# atmega328p_TH.net
KiCad netlist of a schematic drawn in EAGLE
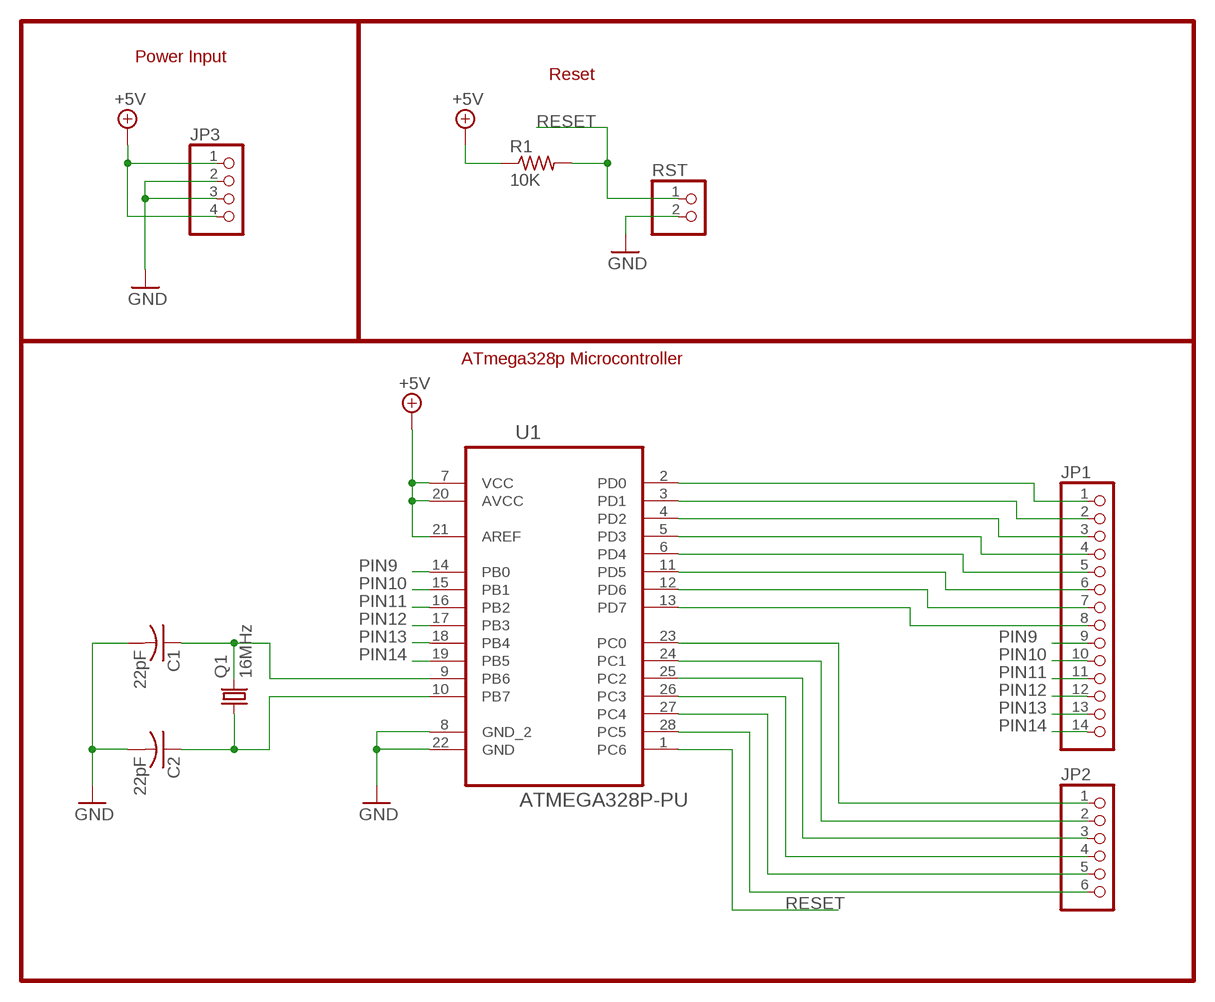
[diagram p0: schematic, sheet 1]

(export (version "E")
  (design (tool "Eeschema 10.0.6"))
  (components
    (comp (ref "C1")
      (value "22pF")
      (footprint "eagle-import:C025-024X044")
      (libsource (lib "eagle-import") (part "C-US025-024X044"))
    )
    (comp (ref "C2")
      (value "22pF")
      (footprint "eagle-import:C025-024X044")
      (libsource (lib "eagle-import") (part "C-US025-024X044"))
    )
    (comp (ref "JP1")
      (value "PINHD-1X14")
      (footprint "eagle-import:1X14")
      (libsource (lib "eagle-import") (part "PINHD-1X14"))
    )
    (comp (ref "JP2")
      (value "PINHD-1X6")
      (footprint "eagle-import:1X06")
      (libsource (lib "eagle-import") (part "PINHD-1X6"))
    )
    (comp (ref "JP3")
      (value "PINHD-1X4")
      (footprint "eagle-import:1X04")
      (libsource (lib "eagle-import") (part "PINHD-1X4"))
    )
    (comp (ref "Q1")
      (value "16MHz")
      (footprint "eagle-import:HC49_S")
      (libsource (lib "eagle-import") (part "CRYSTALHC49S"))
    )
    (comp (ref "R1")
      (value "10K")
      (footprint "eagle-import:0204_7")
      (libsource (lib "eagle-import") (part "R-US_0204/7"))
    )
    (comp (ref "RST")
      (value "PINHD-1X2")
      (footprint "eagle-import:1X02")
      (libsource (lib "eagle-import") (part "PINHD-1X2"))
    )
    (comp (ref "U1")
      (value "ATMEGA328P-PU")
      (footprint "eagle-import:DIP254P762X457-28")
      (libsource (lib "eagle-import") (part "ATMEGA328P-PU"))
    )
  )
  (nets
    (net (code "1") (name "+5V") (class "Default")
      (node (ref "JP3") (pin "1") (pinfunction "1_1") (pintype "passive"))
      (node (ref "JP3") (pin "4") (pinfunction "4_4") (pintype "passive"))
      (node (ref "R1") (pin "1") (pinfunction "1_1") (pintype "passive"))
      (node (ref "U1") (pin "20") (pinfunction "AVCC_20") (pintype "power_in"))
      (node (ref "U1") (pin "21") (pinfunction "AREF_21") (pintype "input"))
      (node (ref "U1") (pin "7") (pinfunction "VCC_7") (pintype "power_in"))
    )
    (net (code "2") (name "/PIN9") (class "Default")
      (node (ref "JP1") (pin "9") (pinfunction "9_9") (pintype "passive"))
      (node (ref "U1") (pin "14") (pinfunction "PB0_14") (pintype "bidirectional"))
    )
    (net (code "3") (name "/PIN10") (class "Default")
      (node (ref "JP1") (pin "10") (pinfunction "10_10") (pintype "passive"))
      (node (ref "U1") (pin "15") (pinfunction "PB1_15") (pintype "bidirectional"))
    )
    (net (code "4") (name "/PIN11") (class "Default")
      (node (ref "JP1") (pin "11") (pinfunction "11_11") (pintype "passive"))
      (node (ref "U1") (pin "16") (pinfunction "PB2_16") (pintype "bidirectional"))
    )
    (net (code "5") (name "/PIN12") (class "Default")
      (node (ref "JP1") (pin "12") (pinfunction "12_12") (pintype "passive"))
      (node (ref "U1") (pin "17") (pinfunction "PB3_17") (pintype "bidirectional"))
    )
    (net (code "6") (name "/PIN13") (class "Default")
      (node (ref "JP1") (pin "13") (pinfunction "13_13") (pintype "passive"))
      (node (ref "U1") (pin "18") (pinfunction "PB4_18") (pintype "bidirectional"))
    )
    (net (code "7") (name "/PIN14") (class "Default")
      (node (ref "JP1") (pin "14") (pinfunction "14_14") (pintype "passive"))
      (node (ref "U1") (pin "19") (pinfunction "PB5_19") (pintype "bidirectional"))
    )
    (net (code "8") (name "/RESET") (class "Default")
      (node (ref "R1") (pin "2") (pinfunction "2_2") (pintype "passive"))
      (node (ref "RST") (pin "1") (pinfunction "1_1") (pintype "passive"))
      (node (ref "U1") (pin "1") (pinfunction "PC6_1") (pintype "bidirectional"))
    )
    (net (code "9") (name "GND") (class "Default")
      (node (ref "C1") (pin "2") (pinfunction "2_2") (pintype "passive"))
      (node (ref "C2") (pin "2") (pinfunction "2_2") (pintype "passive"))
      (node (ref "JP3") (pin "2") (pinfunction "2_2") (pintype "passive"))
      (node (ref "JP3") (pin "3") (pinfunction "3_3") (pintype "passive"))
      (node (ref "RST") (pin "2") (pinfunction "2_2") (pintype "passive"))
      (node (ref "U1") (pin "22") (pinfunction "GND_22") (pintype "passive"))
      (node (ref "U1") (pin "8") (pinfunction "GND_2_8") (pintype "passive"))
    )
    (net (code "10") (name "Net-(U1-PB6)") (class "Default")
      (node (ref "C1") (pin "1") (pinfunction "1_1") (pintype "passive"))
      (node (ref "Q1") (pin "2") (pinfunction "2_2") (pintype "passive"))
      (node (ref "U1") (pin "9") (pinfunction "PB6_9") (pintype "bidirectional"))
    )
    (net (code "11") (name "Net-(U1-PB7)") (class "Default")
      (node (ref "C2") (pin "1") (pinfunction "1_1") (pintype "passive"))
      (node (ref "Q1") (pin "1") (pinfunction "1_1") (pintype "passive"))
      (node (ref "U1") (pin "10") (pinfunction "PB7_10") (pintype "bidirectional"))
    )
    (net (code "12") (name "Net-(U1-PC0)") (class "Default")
      (node (ref "JP2") (pin "1") (pinfunction "1_1") (pintype "passive"))
      (node (ref "U1") (pin "23") (pinfunction "PC0_23") (pintype "bidirectional"))
    )
    (net (code "13") (name "Net-(U1-PC1)") (class "Default")
      (node (ref "JP2") (pin "2") (pinfunction "2_2") (pintype "passive"))
      (node (ref "U1") (pin "24") (pinfunction "PC1_24") (pintype "bidirectional"))
    )
    (net (code "14") (name "Net-(U1-PC2)") (class "Default")
      (node (ref "JP2") (pin "3") (pinfunction "3_3") (pintype "passive"))
      (node (ref "U1") (pin "25") (pinfunction "PC2_25") (pintype "bidirectional"))
    )
    (net (code "15") (name "Net-(U1-PC3)") (class "Default")
      (node (ref "JP2") (pin "4") (pinfunction "4_4") (pintype "passive"))
      (node (ref "U1") (pin "26") (pinfunction "PC3_26") (pintype "bidirectional"))
    )
    (net (code "16") (name "Net-(U1-PC4)") (class "Default")
      (node (ref "JP2") (pin "5") (pinfunction "5_5") (pintype "passive"))
      (node (ref "U1") (pin "27") (pinfunction "PC4_27") (pintype "bidirectional"))
    )
    (net (code "17") (name "Net-(U1-PC5)") (class "Default")
      (node (ref "JP2") (pin "6") (pinfunction "6_6") (pintype "passive"))
      (node (ref "U1") (pin "28") (pinfunction "PC5_28") (pintype "bidirectional"))
    )
    (net (code "18") (name "Net-(U1-PD0)") (class "Default")
      (node (ref "JP1") (pin "1") (pinfunction "1_1") (pintype "passive"))
      (node (ref "U1") (pin "2") (pinfunction "PD0_2") (pintype "bidirectional"))
    )
    (net (code "19") (name "Net-(U1-PD1)") (class "Default")
      (node (ref "JP1") (pin "2") (pinfunction "2_2") (pintype "passive"))
      (node (ref "U1") (pin "3") (pinfunction "PD1_3") (pintype "bidirectional"))
    )
    (net (code "20") (name "Net-(U1-PD2)") (class "Default")
      (node (ref "JP1") (pin "3") (pinfunction "3_3") (pintype "passive"))
      (node (ref "U1") (pin "4") (pinfunction "PD2_4") (pintype "bidirectional"))
    )
    (net (code "21") (name "Net-(U1-PD3)") (class "Default")
      (node (ref "JP1") (pin "4") (pinfunction "4_4") (pintype "passive"))
      (node (ref "U1") (pin "5") (pinfunction "PD3_5") (pintype "bidirectional"))
    )
    (net (code "22") (name "Net-(U1-PD4)") (class "Default")
      (node (ref "JP1") (pin "5") (pinfunction "5_5") (pintype "passive"))
      (node (ref "U1") (pin "6") (pinfunction "PD4_6") (pintype "bidirectional"))
    )
    (net (code "23") (name "Net-(U1-PD5)") (class "Default")
      (node (ref "JP1") (pin "6") (pinfunction "6_6") (pintype "passive"))
      (node (ref "U1") (pin "11") (pinfunction "PD5_11") (pintype "bidirectional"))
    )
    (net (code "24") (name "Net-(U1-PD6)") (class "Default")
      (node (ref "JP1") (pin "7") (pinfunction "7_7") (pintype "passive"))
      (node (ref "U1") (pin "12") (pinfunction "PD6_12") (pintype "bidirectional"))
    )
    (net (code "25") (name "Net-(U1-PD7)") (class "Default")
      (node (ref "JP1") (pin "8") (pinfunction "8_8") (pintype "passive"))
      (node (ref "U1") (pin "13") (pinfunction "PD7_13") (pintype "bidirectional"))
    )
  )
)
